# 4313_Xbee_V1_0.net
KiCad netlist of a schematic drawn in EAGLE
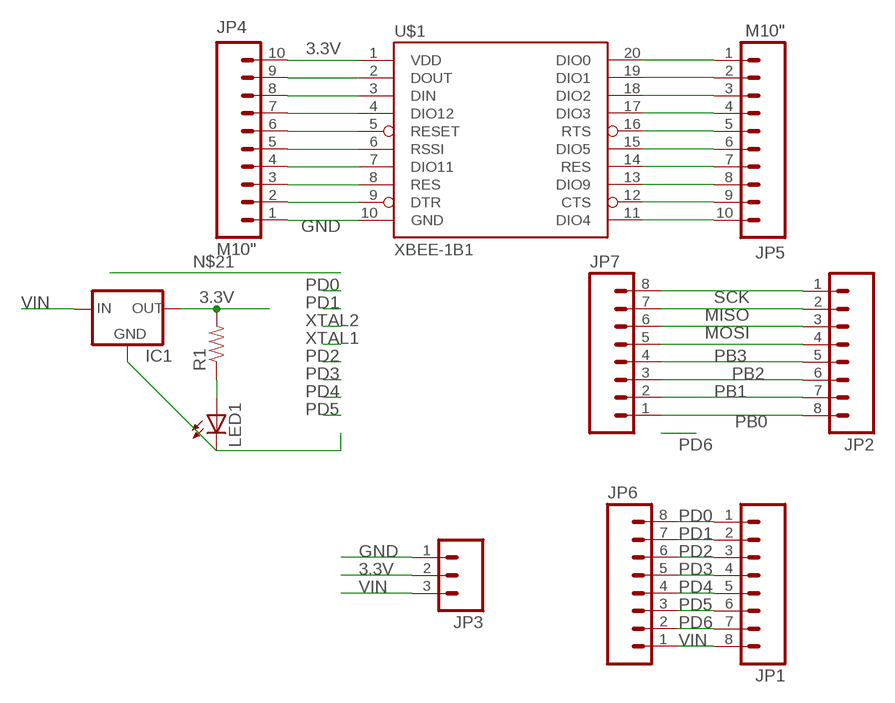
[diagram p0: schematic, sheet 1]

(export (version "E")
  (design (tool "Eeschema 10.0.6"))
  (components
    (comp (ref "IC1")
      (value "V_REG_78XXSIDE")
      (footprint "eagle-import:78XXL")
      (libsource (lib "eagle-import") (part "V_REG_78XXSIDE"))
    )
    (comp (ref "JP1")
      (value "M081X08")
      (footprint "eagle-import:1X08")
      (libsource (lib "eagle-import") (part "M081X08"))
    )
    (comp (ref "JP2")
      (value "M081X08")
      (footprint "eagle-import:1X08")
      (libsource (lib "eagle-import") (part "M081X08"))
    )
    (comp (ref "JP3")
      (value "M03PTH")
      (footprint "eagle-import:1X03")
      (libsource (lib "eagle-import") (part "M03PTH"))
    )
    (comp (ref "JP4")
      (value "M10\"")
      (footprint "eagle-import:1X10")
      (libsource (lib "eagle-import") (part "M10{dblquote}"))
    )
    (comp (ref "JP5")
      (value "M10\"")
      (footprint "eagle-import:1X10")
      (libsource (lib "eagle-import") (part "M10{dblquote}"))
    )
    (comp (ref "JP6")
      (value "M081X08")
      (footprint "eagle-import:1X08")
      (libsource (lib "eagle-import") (part "M081X08"))
    )
    (comp (ref "JP7")
      (value "M081X08")
      (footprint "eagle-import:1X08")
      (libsource (lib "eagle-import") (part "M081X08"))
    )
    (comp (ref "LED1")
      (value "LED1206")
      (footprint "eagle-import:LED-1206")
      (libsource (lib "eagle-import") (part "LED1206"))
    )
    (comp (ref "R1")
      (value "RESISTOR1206")
      (footprint "eagle-import:1206")
      (libsource (lib "eagle-import") (part "RESISTOR1206"))
    )
    (comp (ref "U$1")
      (value "XBEE-1B1")
      (footprint "eagle-import:XBEE-1")
      (libsource (lib "eagle-import") (part "XBEE-1B1"))
    )
  )
  (nets
    (net (code "1") (name "/3.3V") (class "Default")
      (node (ref "IC1") (pin "OUT") (pinfunction "OUT_OUT") (pintype "output"))
      (node (ref "JP3") (pin "2") (pinfunction "2_2") (pintype "passive"))
      (node (ref "JP4") (pin "10") (pinfunction "10_10") (pintype "passive"))
      (node (ref "R1") (pin "2") (pinfunction "2_2") (pintype "passive"))
      (node (ref "U$1") (pin "1") (pinfunction "VDD_1") (pintype "power_in"))
    )
    (net (code "2") (name "/GND") (class "Default")
      (node (ref "IC1") (pin "GND") (pinfunction "GND_GND") (pintype "input"))
      (node (ref "JP3") (pin "1") (pinfunction "1_1") (pintype "passive"))
      (node (ref "JP4") (pin "1") (pinfunction "1_1") (pintype "passive"))
      (node (ref "LED1") (pin "C") (pinfunction "C_C") (pintype "passive"))
      (node (ref "U$1") (pin "10") (pinfunction "GND_10") (pintype "power_in"))
    )
    (net (code "3") (name "/MISO") (class "Default")
      (node (ref "JP2") (pin "2") (pinfunction "2_2") (pintype "passive"))
      (node (ref "JP7") (pin "7") (pinfunction "7_7") (pintype "passive"))
    )
    (net (code "4") (name "/MOSI") (class "Default")
      (node (ref "JP2") (pin "3") (pinfunction "3_3") (pintype "passive"))
      (node (ref "JP7") (pin "6") (pinfunction "6_6") (pintype "passive"))
    )
    (net (code "6") (name "/PB0") (class "Default")
      (node (ref "JP2") (pin "8") (pinfunction "8_8") (pintype "passive"))
      (node (ref "JP7") (pin "1") (pinfunction "1_1") (pintype "passive"))
    )
    (net (code "7") (name "/PB1") (class "Default")
      (node (ref "JP2") (pin "7") (pinfunction "7_7") (pintype "passive"))
      (node (ref "JP7") (pin "2") (pinfunction "2_2") (pintype "passive"))
    )
    (net (code "8") (name "/PB2") (class "Default")
      (node (ref "JP2") (pin "6") (pinfunction "6_6") (pintype "passive"))
      (node (ref "JP7") (pin "3") (pinfunction "3_3") (pintype "passive"))
    )
    (net (code "9") (name "/PB3") (class "Default")
      (node (ref "JP2") (pin "5") (pinfunction "5_5") (pintype "passive"))
      (node (ref "JP7") (pin "4") (pinfunction "4_4") (pintype "passive"))
    )
    (net (code "10") (name "/PD0") (class "Default")
      (node (ref "JP1") (pin "1") (pinfunction "1_1") (pintype "passive"))
      (node (ref "JP6") (pin "8") (pinfunction "8_8") (pintype "passive"))
    )
    (net (code "11") (name "/PD1") (class "Default")
      (node (ref "JP1") (pin "2") (pinfunction "2_2") (pintype "passive"))
      (node (ref "JP6") (pin "7") (pinfunction "7_7") (pintype "passive"))
    )
    (net (code "12") (name "/PD2") (class "Default")
      (node (ref "JP1") (pin "3") (pinfunction "3_3") (pintype "passive"))
      (node (ref "JP6") (pin "6") (pinfunction "6_6") (pintype "passive"))
    )
    (net (code "13") (name "/PD3") (class "Default")
      (node (ref "JP1") (pin "4") (pinfunction "4_4") (pintype "passive"))
      (node (ref "JP6") (pin "5") (pinfunction "5_5") (pintype "passive"))
    )
    (net (code "14") (name "/PD4") (class "Default")
      (node (ref "JP1") (pin "5") (pinfunction "5_5") (pintype "passive"))
      (node (ref "JP6") (pin "4") (pinfunction "4_4") (pintype "passive"))
    )
    (net (code "15") (name "/PD5") (class "Default")
      (node (ref "JP1") (pin "6") (pinfunction "6_6") (pintype "passive"))
      (node (ref "JP6") (pin "3") (pinfunction "3_3") (pintype "passive"))
    )
    (net (code "16") (name "/PD6") (class "Default")
      (node (ref "JP1") (pin "7") (pinfunction "7_7") (pintype "passive"))
      (node (ref "JP6") (pin "2") (pinfunction "2_2") (pintype "passive"))
    )
    (net (code "17") (name "/SCK") (class "Default")
      (node (ref "JP2") (pin "1") (pinfunction "1_1") (pintype "passive"))
      (node (ref "JP7") (pin "8") (pinfunction "8_8") (pintype "passive"))
    )
    (net (code "18") (name "/VIN") (class "Default")
      (node (ref "IC1") (pin "IN") (pinfunction "IN_IN") (pintype "input"))
      (node (ref "JP1") (pin "8") (pinfunction "8_8") (pintype "passive"))
      (node (ref "JP3") (pin "3") (pinfunction "3_3") (pintype "passive"))
      (node (ref "JP6") (pin "1") (pinfunction "1_1") (pintype "passive"))
    )
    (net (code "21") (name "Net-(JP2-Pad4)") (class "Default")
      (node (ref "JP2") (pin "4") (pinfunction "4_4") (pintype "passive"))
      (node (ref "JP7") (pin "5") (pinfunction "5_5") (pintype "passive"))
    )
    (net (code "22") (name "Net-(JP4-Pad3)") (class "Default")
      (node (ref "JP4") (pin "3") (pinfunction "3_3") (pintype "passive"))
      (node (ref "U$1") (pin "8") (pinfunction "RES_8") (pintype "bidirectional"))
    )
    (net (code "23") (name "Net-(JP5-Pad7)") (class "Default")
      (node (ref "JP5") (pin "7") (pinfunction "7_7") (pintype "passive"))
      (node (ref "U$1") (pin "14") (pinfunction "RES_14") (pintype "bidirectional"))
    )
    (net (code "24") (name "Net-(LED1-PadA)") (class "Default")
      (node (ref "LED1") (pin "A") (pinfunction "A_A") (pintype "passive"))
      (node (ref "R1") (pin "1") (pinfunction "1_1") (pintype "passive"))
    )
    (net (code "25") (name "Net-(U$1-CTS)") (class "Default")
      (node (ref "JP5") (pin "9") (pinfunction "9_9") (pintype "passive"))
      (node (ref "U$1") (pin "12") (pinfunction "CTS_12") (pintype "output"))
    )
    (net (code "26") (name "Net-(U$1-DIN)") (class "Default")
      (node (ref "JP4") (pin "8") (pinfunction "8_8") (pintype "passive"))
      (node (ref "U$1") (pin "3") (pinfunction "DIN_3") (pintype "input"))
    )
    (net (code "27") (name "Net-(U$1-DIO0)") (class "Default")
      (node (ref "JP5") (pin "1") (pinfunction "1_1") (pintype "passive"))
      (node (ref "U$1") (pin "20") (pinfunction "DIO0_20") (pintype "bidirectional"))
    )
    (net (code "28") (name "Net-(U$1-DIO1)") (class "Default")
      (node (ref "JP5") (pin "2") (pinfunction "2_2") (pintype "passive"))
      (node (ref "U$1") (pin "19") (pinfunction "DIO1_19") (pintype "bidirectional"))
    )
    (net (code "29") (name "Net-(U$1-DIO2)") (class "Default")
      (node (ref "JP5") (pin "3") (pinfunction "3_3") (pintype "passive"))
      (node (ref "U$1") (pin "18") (pinfunction "DIO2_18") (pintype "bidirectional"))
    )
    (net (code "30") (name "Net-(U$1-DIO3)") (class "Default")
      (node (ref "JP5") (pin "4") (pinfunction "4_4") (pintype "passive"))
      (node (ref "U$1") (pin "17") (pinfunction "DIO3_17") (pintype "bidirectional"))
    )
    (net (code "31") (name "Net-(U$1-DIO4)") (class "Default")
      (node (ref "JP5") (pin "10") (pinfunction "10_10") (pintype "passive"))
      (node (ref "U$1") (pin "11") (pinfunction "DIO4_11") (pintype "bidirectional"))
    )
    (net (code "32") (name "Net-(U$1-DIO5)") (class "Default")
      (node (ref "JP5") (pin "6") (pinfunction "6_6") (pintype "passive"))
      (node (ref "U$1") (pin "15") (pinfunction "DIO5_15") (pintype "bidirectional"))
    )
    (net (code "33") (name "Net-(U$1-DIO9)") (class "Default")
      (node (ref "JP5") (pin "8") (pinfunction "8_8") (pintype "passive"))
      (node (ref "U$1") (pin "13") (pinfunction "DIO9_13") (pintype "bidirectional"))
    )
    (net (code "34") (name "Net-(U$1-DIO11)") (class "Default")
      (node (ref "JP4") (pin "4") (pinfunction "4_4") (pintype "passive"))
      (node (ref "U$1") (pin "7") (pinfunction "DIO11_7") (pintype "bidirectional"))
    )
    (net (code "35") (name "Net-(U$1-DIO12)") (class "Default")
      (node (ref "JP4") (pin "7") (pinfunction "7_7") (pintype "passive"))
      (node (ref "U$1") (pin "4") (pinfunction "DIO12_4") (pintype "bidirectional"))
    )
    (net (code "36") (name "Net-(U$1-DOUT)") (class "Default")
      (node (ref "JP4") (pin "9") (pinfunction "9_9") (pintype "passive"))
      (node (ref "U$1") (pin "2") (pinfunction "DOUT_2") (pintype "output"))
    )
    (net (code "37") (name "Net-(U$1-DTR)") (class "Default")
      (node (ref "JP4") (pin "2") (pinfunction "2_2") (pintype "passive"))
      (node (ref "U$1") (pin "9") (pinfunction "DTR_9") (pintype "bidirectional"))
    )
    (net (code "38") (name "Net-(U$1-RESET)") (class "Default")
      (node (ref "JP4") (pin "6") (pinfunction "6_6") (pintype "passive"))
      (node (ref "U$1") (pin "5") (pinfunction "RESET_5") (pintype "input"))
    )
    (net (code "39") (name "Net-(U$1-RSSI)") (class "Default")
      (node (ref "JP4") (pin "5") (pinfunction "5_5") (pintype "passive"))
      (node (ref "U$1") (pin "6") (pinfunction "RSSI_6") (pintype "bidirectional"))
    )
    (net (code "40") (name "Net-(U$1-RTS)") (class "Default")
      (node (ref "JP5") (pin "5") (pinfunction "5_5") (pintype "passive"))
      (node (ref "U$1") (pin "16") (pinfunction "RTS_16") (pintype "input"))
    )
  )
)
